# probe.net
KiCad netlist of a schematic drawn in EAGLE
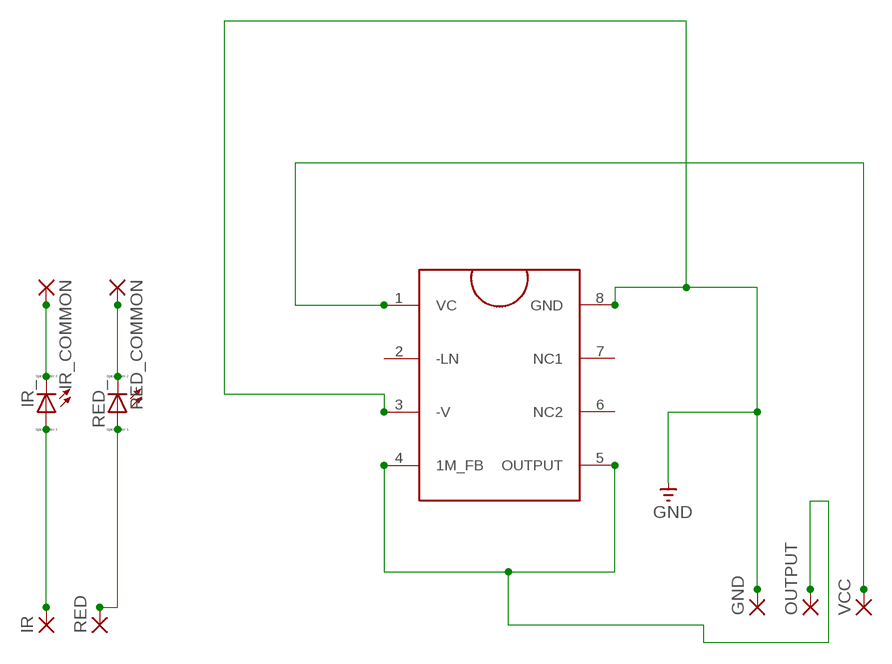
[diagram p0: schematic, sheet 1]

(export (version "E")
  (design (tool "Eeschema 10.0.6"))
  (components
    (comp (ref "GND")
      (value "SMD2")
      (footprint "eagle-import:SMD1,27-2,54")
      (libsource (lib "eagle-import") (part "SMD2"))
    )
    (comp (ref "IR")
      (value "SMD2")
      (footprint "eagle-import:SMD1,27-2,54")
      (libsource (lib "eagle-import") (part "SMD2"))
    )
    (comp (ref "IR_")
      (value "LED_E")
      (footprint "eagle-import:LED_1206")
      (libsource (lib "eagle-import") (part "LED_E"))
    )
    (comp (ref "IR_COMMON")
      (value "SMD2")
      (footprint "eagle-import:SMD1,27-2,54")
      (libsource (lib "eagle-import") (part "SMD2"))
    )
    (comp (ref "OUTPUT")
      (value "SMD2")
      (footprint "eagle-import:SMD1,27-2,54")
      (libsource (lib "eagle-import") (part "SMD2"))
    )
    (comp (ref "RED")
      (value "SMD2")
      (footprint "eagle-import:SMD1,27-2,54")
      (libsource (lib "eagle-import") (part "SMD2"))
    )
    (comp (ref "RED_")
      (value "LED_E")
      (footprint "eagle-import:LED_1206")
      (libsource (lib "eagle-import") (part "LED_E"))
    )
    (comp (ref "RED_COMMON")
      (value "SMD2")
      (footprint "eagle-import:SMD1,27-2,54")
      (libsource (lib "eagle-import") (part "SMD2"))
    )
    (comp (ref "U$1")
      (value "OPT101")
      (footprint "eagle-import:SO8")
      (libsource (lib "eagle-import") (part "OPT101"))
    )
    (comp (ref "VCC")
      (value "SMD2")
      (footprint "eagle-import:SMD1,27-2,54")
      (libsource (lib "eagle-import") (part "SMD2"))
    )
  )
  (nets
    (net (code "1") (name "GND") (class "Default")
      (node (ref "GND") (pin "1") (pinfunction "P_1") (pintype "passive"))
      (node (ref "U$1") (pin "3") (pinfunction "-V_3") (pintype "input"))
      (node (ref "U$1") (pin "8") (pinfunction "GND_8") (pintype "input"))
    )
    (net (code "2") (name "Net-(IR-P)") (class "Default")
      (node (ref "IR") (pin "1") (pinfunction "P_1") (pintype "passive"))
      (node (ref "IR_") (pin "A") (pinfunction "A_A") (pintype "passive"))
    )
    (net (code "3") (name "Net-(IR_COMMON-P)") (class "Default")
      (node (ref "IR_") (pin "C") (pinfunction "C_C") (pintype "passive"))
      (node (ref "IR_COMMON") (pin "1") (pinfunction "P_1") (pintype "passive"))
    )
    (net (code "4") (name "Net-(OUTPUT-P)") (class "Default")
      (node (ref "OUTPUT") (pin "1") (pinfunction "P_1") (pintype "passive"))
      (node (ref "U$1") (pin "4") (pinfunction "1M_FB_4") (pintype "input"))
      (node (ref "U$1") (pin "5") (pinfunction "OUTPUT_5") (pintype "output"))
    )
    (net (code "5") (name "Net-(RED-P)") (class "Default")
      (node (ref "RED") (pin "1") (pinfunction "P_1") (pintype "passive"))
      (node (ref "RED_") (pin "A") (pinfunction "A_A") (pintype "passive"))
    )
    (net (code "6") (name "Net-(RED_COMMON-P)") (class "Default")
      (node (ref "RED_") (pin "C") (pinfunction "C_C") (pintype "passive"))
      (node (ref "RED_COMMON") (pin "1") (pinfunction "P_1") (pintype "passive"))
    )
    (net (code "7") (name "Net-(U$1-VC)") (class "Default")
      (node (ref "U$1") (pin "1") (pinfunction "VC_1") (pintype "input"))
      (node (ref "VCC") (pin "1") (pinfunction "P_1") (pintype "passive"))
    )
    (net (code "8") (name "unconnected-(U$1--LN-Pad2)") (class "Default")
      (node (ref "U$1") (pin "2") (pinfunction "-LN_2") (pintype "input"))
    )
    (net (code "9") (name "unconnected-(U$1-NC1-Pad7)") (class "Default")
      (node (ref "U$1") (pin "7") (pinfunction "NC1_7") (pintype "no_connect"))
    )
    (net (code "10") (name "unconnected-(U$1-NC2-Pad6)") (class "Default")
      (node (ref "U$1") (pin "6") (pinfunction "NC2_6") (pintype "no_connect"))
    )
  )
)
